# Stabilizer_Pounder.net
KiCad netlist of a schematic drawn in Altium Designer
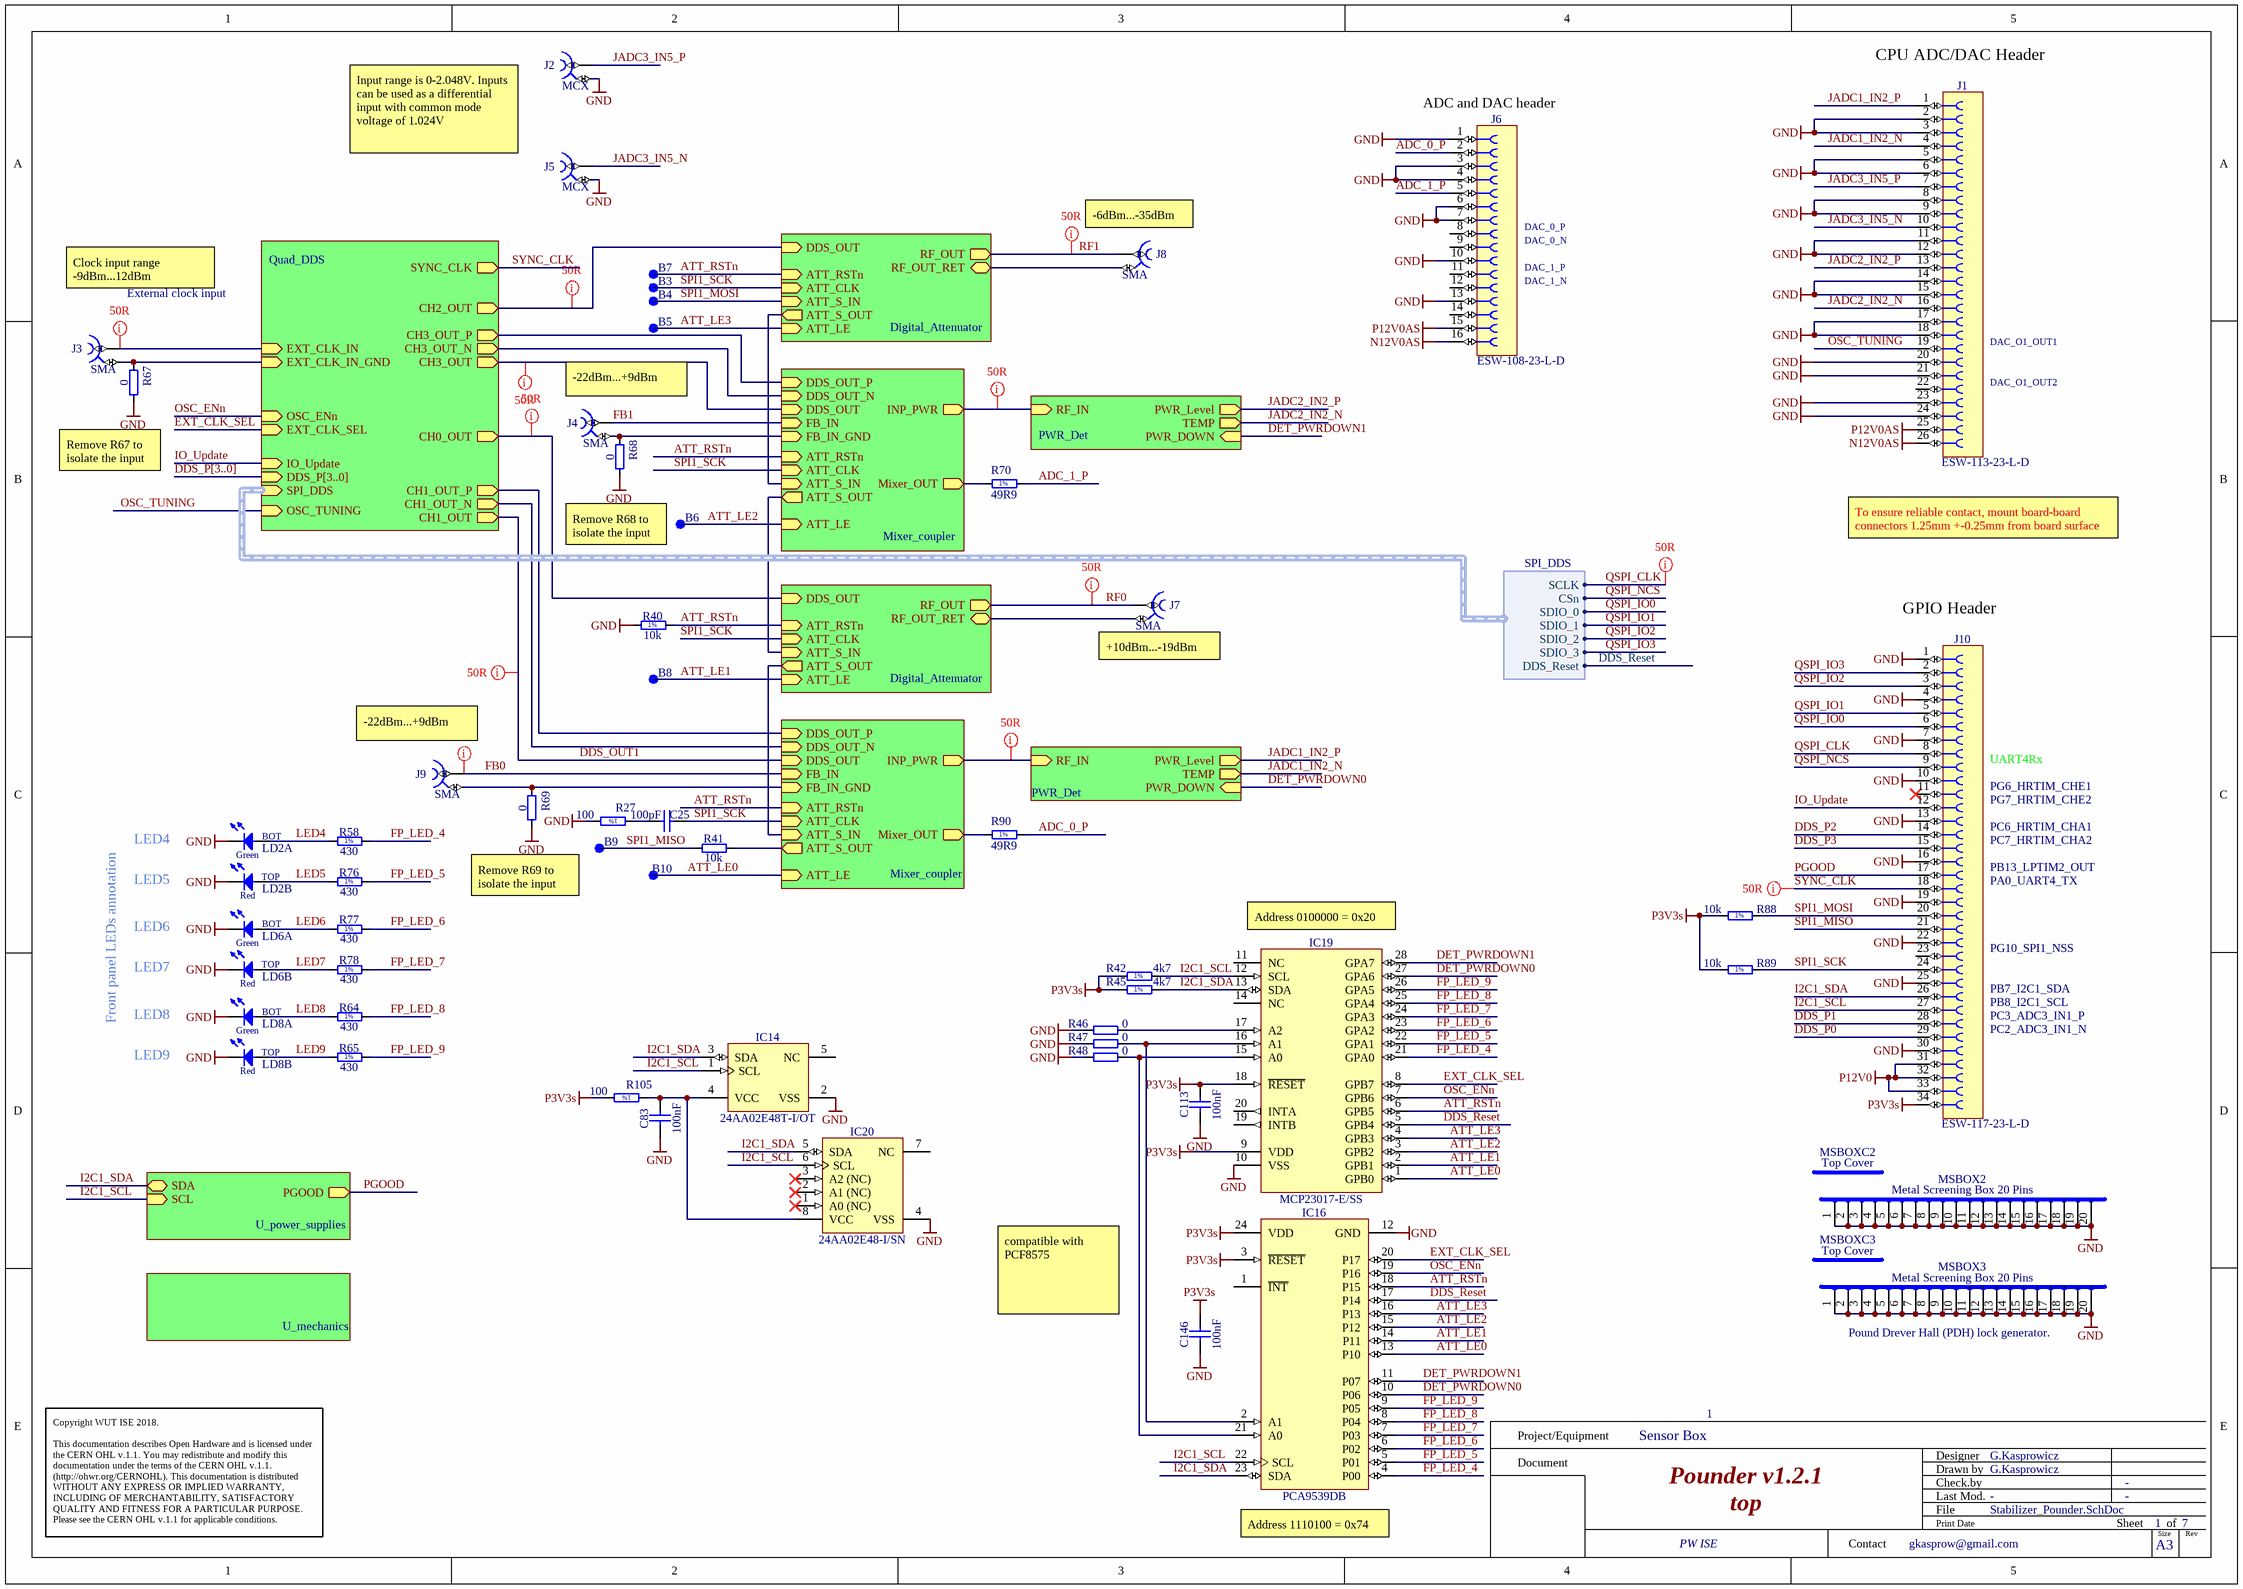
[diagram p0: Stabilizer_Pounder.SchDoc]

(export (version "E")
  (design (tool "Eeschema 10.0.6"))
  (components
    (comp (ref "B3")
      (value "SMD Pad")
      (footprint "C100")
      (description "Through Hole Pad")
      (fields (field (name "PART NUMBER") "SMD_PAD_D1MM") (field (name "AUTHOR") "CERN DEM JLC"))
      (libsource (lib "Eletro-mechanical") (part "Single SMD Pad (Round)"))
    )
    (comp (ref "B4")
      (value "SMD Pad")
      (footprint "C100")
      (description "Through Hole Pad")
      (fields (field (name "PART NUMBER") "SMD_PAD_D1MM") (field (name "AUTHOR") "CERN DEM JLC"))
      (libsource (lib "Eletro-mechanical") (part "Single SMD Pad (Round)"))
    )
    (comp (ref "B5")
      (value "SMD Pad")
      (footprint "C100")
      (description "Through Hole Pad")
      (fields (field (name "PART NUMBER") "SMD_PAD_D1MM") (field (name "AUTHOR") "CERN DEM JLC"))
      (libsource (lib "Eletro-mechanical") (part "Single SMD Pad (Round)"))
    )
    (comp (ref "B6")
      (value "SMD Pad")
      (footprint "C100")
      (description "Through Hole Pad")
      (fields (field (name "PART NUMBER") "SMD_PAD_D1MM") (field (name "AUTHOR") "CERN DEM JLC"))
      (libsource (lib "Eletro-mechanical") (part "Single SMD Pad (Round)"))
    )
    (comp (ref "B7")
      (value "SMD Pad")
      (footprint "C100")
      (description "Through Hole Pad")
      (fields (field (name "PART NUMBER") "SMD_PAD_D1MM") (field (name "AUTHOR") "CERN DEM JLC"))
      (libsource (lib "Eletro-mechanical") (part "Single SMD Pad (Round)"))
    )
    (comp (ref "B8")
      (value "SMD Pad")
      (footprint "C100")
      (description "Through Hole Pad")
      (fields (field (name "PART NUMBER") "SMD_PAD_D1MM") (field (name "AUTHOR") "CERN DEM JLC"))
      (libsource (lib "Eletro-mechanical") (part "Single SMD Pad (Round)"))
    )
    (comp (ref "B9")
      (value "SMD Pad")
      (footprint "C100")
      (description "Through Hole Pad")
      (fields (field (name "PART NUMBER") "SMD_PAD_D1MM") (field (name "AUTHOR") "CERN DEM JLC"))
      (libsource (lib "Eletro-mechanical") (part "Single SMD Pad (Round)"))
    )
    (comp (ref "B10")
      (value "SMD Pad")
      (footprint "C100")
      (description "Through Hole Pad")
      (fields (field (name "PART NUMBER") "SMD_PAD_D1MM") (field (name "AUTHOR") "CERN DEM JLC"))
      (libsource (lib "Eletro-mechanical") (part "Single SMD Pad (Round)"))
    )
    (comp (ref "C25")
      (value "100pF")
      (footprint "CAPC1005X55N")
      (description "Non-polarised capacitor")
      (fields
        (field (name "PART NUMBER") "CC0402_100PF_50V_5%_C0G")
        (field (name "VOLTAGE") "50V")
        (field (name "AUTHOR") "CERN DEM JLC")
      )
      (libsource (lib "Capacitors") (part "Capacitor - non polarized"))
    )
    (comp (ref "C83")
      (value "100nF")
      (footprint "CAPC1005X55N")
      (description "Non-polarised capacitor")
      (fields
        (field (name "PART NUMBER") "CC0402_100NF_16V_10%_X5R")
        (field (name "VOLTAGE") "16V")
        (field (name "AUTHOR") "CERN DEM JLC")
      )
      (libsource (lib "Capacitors") (part "Capacitor - non polarized"))
    )
    (comp (ref "C113")
      (value "100nF")
      (footprint "CAPC1005X55N")
      (description "Non-polarised capacitor")
      (fields
        (field (name "PART NUMBER") "CC0402_100NF_16V_10%_X5R")
        (field (name "VOLTAGE") "16V")
        (field (name "AUTHOR") "CERN DEM JLC")
      )
      (libsource (lib "Capacitors") (part "Capacitor - non polarized"))
    )
    (comp (ref "C146")
      (value "100nF")
      (footprint "CAPC1005X55N")
      (description "Non-polarised capacitor")
      (fields
        (field (name "PART NUMBER") "CC0402_100NF_16V_10%_X5R")
        (field (name "VOLTAGE") "16V")
        (field (name "AUTHOR") "CERN DEM JLC")
      )
      (libsource (lib "Capacitors") (part "Capacitor - non polarized"))
    )
    (comp (ref "IC14")
      (value "24AA02E48T-I/OT")
      (footprint "SOT95P280X145-5N")
      (description "1.7V-5.5V, 2K I2C Serial EEPROM With EUI-48 Node Identity")
      (fields (field (name "MANUFACTURER") "MICROCHIP TECHNOLOGY") (field (name "AUTHOR") "CERN DEM MR"))
      (libsource (lib "ICs And Semiconductors") (part "24AA02E48T-I/OT"))
    )
    (comp (ref "IC16")
      (value "PCA9539DB")
      (footprint "SOP65P780X200-24N")
      (fields (field (name "MANUFACTURER") "TEXAS INSTRUMENTS") (field (name "AUTHOR") "CERN DEM HF"))
      (libsource (lib "ICs And Semiconductors") (part "PCA9539DB"))
    )
    (comp (ref "IC19")
      (value "MCP23017-E/SS")
      (footprint "SOP65P780X200-28N")
      (description "16-bit I/O Port Expander With Serial Interface")
      (fields (field (name "MANUFACTURER") "MICROCHIP TECHNOLOGY") (field (name "AUTHOR") "CERN DEM JLC"))
      (libsource (lib "ICs And Semiconductors") (part "MCP23017-E/SS"))
    )
    (comp (ref "IC20")
      (value "24AA02E48-I/SN")
      (footprint "SOIC127P600X175-8N")
      (description "1.7V-5.5V, 2K I2C™ Serial EEPROMs with EUI-48™ Node Identity")
      (fields (field (name "MANUFACTURER") "MICROCHIP TECHNOLOGY") (field (name "AUTHOR") "CERN DEM MR"))
      (libsource (lib "ICS-logic") (part "MEM_24AA02E48-I/SN"))
    )
    (comp (ref "J1")
      (value "ESW-113-23-L-D")
      (footprint "connectors:ESW-113-23-L-D")
      (description "Connector Elevated Socket 26 POS 2.54mm, 13.59mm height")
      (fields
        (field (name "MANUFACTURER") "Samtec")
        (field (name "MANUFACTURER PART NUMBER") "ESW-113-23-L-D")
      )
      (libsource (lib "connectors") (part "ESW-113-23-L-D"))
    )
    (comp (ref "J2")
      (value "MCX")
      (footprint "AMPHENOL_919-383J-51A")
      (fields
        (field (name "PART NUMBER") "AMPHENOL_919-383J-51A")
        (field (name "MANUFACTURER") "AMPHENOL")
        (field (name "MANUFACTURER PART NUMBER") "919-383J-51A")
        (field (name "AUTHOR") "CERN DEM BC")
      )
      (libsource (lib "Connectors") (part "Coax_1Female_1Shield"))
    )
    (comp (ref "J3")
      (value "SMA")
      (footprint "DELOCK_65848")
      (description "50 Ohm Through Hole SMA Right Angle PCB Jack")
      (fields
        (field (name "PART NUMBER") "DELOCK_65848")
        (field (name "MANUFACTURER") "DELOCK")
        (field (name "AUTHOR") "GK")
      )
      (libsource (lib "Connectors") (part "CON_SMA_DELOCK_65848"))
    )
    (comp (ref "J4")
      (value "SMA")
      (footprint "DELOCK_65848")
      (description "50 Ohm Through Hole SMA Right Angle PCB Jack")
      (fields
        (field (name "PART NUMBER") "DELOCK_65848")
        (field (name "MANUFACTURER") "DELOCK")
        (field (name "AUTHOR") "GK")
      )
      (libsource (lib "Connectors") (part "CON_SMA_DELOCK_65848"))
    )
    (comp (ref "J5")
      (value "MCX")
      (footprint "AMPHENOL_919-383J-51A")
      (fields
        (field (name "PART NUMBER") "AMPHENOL_919-383J-51A")
        (field (name "MANUFACTURER") "AMPHENOL")
        (field (name "MANUFACTURER PART NUMBER") "919-383J-51A")
        (field (name "AUTHOR") "CERN DEM BC")
      )
      (libsource (lib "Connectors") (part "Coax_1Female_1Shield"))
    )
    (comp (ref "J6")
      (value "ESW-108-23-L-D")
      (footprint "connectors:ESW-108-23-L-D")
      (description "Connector Elevated Socket 16 POS 2.54mm, 13.59mm height")
      (fields
        (field (name "MANUFACTURER") "Samtec")
        (field (name "MANUFACTURER PART NUMBER") "ESW-108-23-L-D")
      )
      (libsource (lib "connectors") (part "ESW-108-23-L-D"))
    )
    (comp (ref "J7")
      (value "SMA")
      (footprint "DELOCK_65848")
      (description "50 Ohm Through Hole SMA Right Angle PCB Jack")
      (fields
        (field (name "PART NUMBER") "DELOCK_65848")
        (field (name "MANUFACTURER") "DELOCK")
        (field (name "AUTHOR") "GK")
      )
      (libsource (lib "") (part "CON_SMA_DELOCK_65848_1"))
    )
    (comp (ref "J8")
      (value "SMA")
      (footprint "DELOCK_65848")
      (description "50 Ohm Through Hole SMA Right Angle PCB Jack")
      (fields
        (field (name "PART NUMBER") "DELOCK_65848")
        (field (name "MANUFACTURER") "DELOCK")
        (field (name "AUTHOR") "GK")
      )
      (libsource (lib "") (part "CON_SMA_DELOCK_65848_1"))
    )
    (comp (ref "J9")
      (value "SMA")
      (footprint "DELOCK_65848")
      (description "50 Ohm Through Hole SMA Right Angle PCB Jack")
      (fields
        (field (name "PART NUMBER") "DELOCK_65848")
        (field (name "MANUFACTURER") "DELOCK")
        (field (name "AUTHOR") "GK")
      )
      (libsource (lib "Connectors") (part "CON_SMA_DELOCK_65848"))
    )
    (comp (ref "J10")
      (value "ESW-117-23-L-D")
      (footprint "connectors:ESW-117-23-L-D")
      (description "Connector Elevated Socket 34 POS 2.54mm, 13.59mm height")
      (fields
        (field (name "MANUFACTURER") "Samtec")
        (field (name "MANUFACTURER PART NUMBER") "ESW-117-23-L-D")
      )
      (libsource (lib "connectors") (part "ESW-117-23-L-D"))
    )
    (comp (ref "LD2")
      (value "Red/Green")
      (footprint "LED_DIALIGHT_571-0112F")
      (description "2x LED  Botom Green, Top Red")
      (fields
        (field (name "PART NUMBER") "LED_DIALIGHT_571-0112F")
        (field (name "MANUFACTURER") "DIALIGHT")
        (field (name "AUTHOR") "CERN DEM JLC")
      )
      (libsource (lib "ICs And Semiconductors") (part "LED x2 G-1C2A-BOT_R-3C4A-TOP"))
    )
    (comp (ref "LD6")
      (value "Red/Green")
      (footprint "LED_DIALIGHT_571-0112F")
      (description "2x LED  Botom Green, Top Red")
      (fields
        (field (name "PART NUMBER") "LED_DIALIGHT_571-0112F")
        (field (name "MANUFACTURER") "DIALIGHT")
        (field (name "AUTHOR") "CERN DEM JLC")
      )
      (libsource (lib "ICs And Semiconductors") (part "LED x2 G-1C2A-BOT_R-3C4A-TOP"))
    )
    (comp (ref "LD8")
      (value "Red/Green")
      (footprint "LED_DIALIGHT_571-0112F")
      (description "2x LED  Botom Green, Top Red")
      (fields
        (field (name "PART NUMBER") "LED_DIALIGHT_571-0112F")
        (field (name "MANUFACTURER") "DIALIGHT")
        (field (name "AUTHOR") "CERN DEM JLC")
      )
      (libsource (lib "ICs And Semiconductors") (part "LED x2 G-1C2A-BOT_R-3C4A-TOP"))
    )
    (comp (ref "MSBOX2")
      (value "Metal Screening Box 20 Pins")
      (footprint "MSBOX_LAIRD_BMI-S-205-F")
      (fields
        (field (name "PART NUMBER") "MSBOX_LAIRD_BMI-S-205-F")
        (field (name "MANUFACTURER") "LAIRD")
        (field (name "MANUFACTURER PART NUMBER") "BMI-S-205-F")
        (field (name "AUTHOR") "CERN DEM JLC")
      )
      (libsource (lib "Eletro-mechanical") (part "Metal Screening Box - 20 pins"))
    )
    (comp (ref "MSBOX3")
      (value "Metal Screening Box 20 Pins")
      (footprint "MSBOX_LAIRD_BMI-S-205-F")
      (fields
        (field (name "PART NUMBER") "MSBOX_LAIRD_BMI-S-205-F")
        (field (name "MANUFACTURER") "LAIRD")
        (field (name "MANUFACTURER PART NUMBER") "BMI-S-205-F")
        (field (name "AUTHOR") "CERN DEM JLC")
      )
      (libsource (lib "Eletro-mechanical") (part "Metal Screening Box - 20 pins"))
    )
    (comp (ref "MSBOXC2")
      (value "Top Cover")
      (footprint "MSBOX_LAIRD_BMI-S-205-C")
      (description "Metal Screening Box - Top Cover 0 Pin")
      (fields
        (field (name "PART NUMBER") "MSBOX_LAIRD_BMI-S-205-C")
        (field (name "MANUFACTURER") "LAIRD")
        (field (name "AUTHOR") "CERN DEM JLC")
      )
      (libsource (lib "Eletro-mechanical") (part "Metal Screening Box - Top Cover"))
    )
    (comp (ref "MSBOXC3")
      (value "Top Cover")
      (footprint "MSBOX_LAIRD_BMI-S-205-C")
      (description "Metal Screening Box - Top Cover 0 Pin")
      (fields
        (field (name "PART NUMBER") "MSBOX_LAIRD_BMI-S-205-C")
        (field (name "MANUFACTURER") "LAIRD")
        (field (name "AUTHOR") "CERN DEM JLC")
      )
      (libsource (lib "Eletro-mechanical") (part "Metal Screening Box - Top Cover"))
    )
    (comp (ref "R27")
      (value "100")
      (footprint "RESC1005X40N")
      (description "Resistor - 1%")
      (fields
        (field (name "PART NUMBER") "R0402_100R_1%_0.0625W_100PPM")
        (field (name "POWER") "0.0625W")
        (field (name "AUTHOR") "CERN DEM JLC")
      )
      (libsource (lib "Resistors") (part "Resistor - 1%"))
    )
    (comp (ref "R40")
      (value "10k")
      (footprint "RESC1005X40N")
      (description "Resistor - 1%")
      (fields
        (field (name "PART NUMBER") "R0402_10K_1%_0.0625W_100PPM")
        (field (name "POWER") "0.0625W")
        (field (name "AUTHOR") "CERN DEM JLC")
      )
      (libsource (lib "Resistors") (part "Resistor - 1%"))
    )
    (comp (ref "R41")
      (value "10k")
      (footprint "RESC1005X40N")
      (description "Resistor - 1%")
      (fields
        (field (name "PART NUMBER") "R0402_10K_1%_0.0625W_100PPM")
        (field (name "POWER") "0.0625W")
        (field (name "AUTHOR") "CERN DEM JLC")
      )
      (libsource (lib "") (part "Resistor - 1%_1"))
    )
    (comp (ref "R42")
      (value "4k7")
      (footprint "RESC1005X40N")
      (description "Resistor - 1%")
      (fields
        (field (name "PART NUMBER") "R0402_4K7_1%_0.0625W_100PPM")
        (field (name "POWER") "0.0625W")
        (field (name "AUTHOR") "CERN DEM JLC")
      )
      (libsource (lib "Resistors") (part "Resistor - 1%"))
    )
    (comp (ref "R45")
      (value "4k7")
      (footprint "RESC1005X40N")
      (description "Resistor - 1%")
      (fields
        (field (name "PART NUMBER") "R0402_4K7_1%_0.0625W_100PPM")
        (field (name "POWER") "0.0625W")
        (field (name "AUTHOR") "CERN DEM JLC")
      )
      (libsource (lib "Resistors") (part "Resistor - 1%"))
    )
    (comp (ref "R46")
      (value "0")
      (footprint "RESC1005X40N")
      (description "Resistor")
      (fields
        (field (name "PART NUMBER") "R0402_0R_JUMPER")
        (field (name "MANUFACTURER") "GENERIC")
        (field (name "AUTHOR") "CERN DEM JLC")
      )
      (libsource (lib "Resistors") (part "Resistor"))
    )
    (comp (ref "R47")
      (value "0")
      (footprint "RESC1005X40N")
      (description "Resistor")
      (fields
        (field (name "PART NUMBER") "R0402_0R_JUMPER")
        (field (name "MANUFACTURER") "GENERIC")
        (field (name "AUTHOR") "CERN DEM JLC")
      )
      (libsource (lib "Resistors") (part "Resistor"))
    )
    (comp (ref "R48")
      (value "0")
      (footprint "RESC1005X40N")
      (description "Resistor")
      (fields
        (field (name "PART NUMBER") "R0402_0R_JUMPER")
        (field (name "MANUFACTURER") "GENERIC")
        (field (name "AUTHOR") "CERN DEM JLC")
      )
      (libsource (lib "Resistors") (part "Resistor"))
    )
    (comp (ref "R58")
      (value "430")
      (footprint "RESC1608X55N")
      (description "Resistor - 1%")
      (fields
        (field (name "PART NUMBER") "R0603_430R_1%_0.1W_100PPM")
        (field (name "POWER") "0.1W")
        (field (name "AUTHOR") "CERN DEM JLC")
      )
      (libsource (lib "Resistors") (part "Resistor - 1%"))
    )
    (comp (ref "R64")
      (value "430")
      (footprint "RESC1608X55N")
      (description "Resistor - 1%")
      (fields
        (field (name "PART NUMBER") "R0603_430R_1%_0.1W_100PPM")
        (field (name "POWER") "0.1W")
        (field (name "AUTHOR") "CERN DEM JLC")
      )
      (libsource (lib "Resistors") (part "Resistor - 1%"))
    )
    (comp (ref "R65")
      (value "430")
      (footprint "RESC1608X55N")
      (description "Resistor - 1%")
      (fields
        (field (name "PART NUMBER") "R0603_430R_1%_0.1W_100PPM")
        (field (name "POWER") "0.1W")
        (field (name "AUTHOR") "CERN DEM JLC")
      )
      (libsource (lib "Resistors") (part "Resistor - 1%"))
    )
    (comp (ref "R67")
      (value "0")
      (footprint "RESC1608X55N")
      (description "Resistor")
      (fields
        (field (name "PART NUMBER") "R0603_0R_JUMPER")
        (field (name "MANUFACTURER") "GENERIC")
        (field (name "AUTHOR") "CERN DEM JLC")
      )
      (libsource (lib "Resistors") (part "Resistor"))
    )
    (comp (ref "R68")
      (value "0")
      (footprint "RESC1608X55N")
      (description "Resistor")
      (fields
        (field (name "PART NUMBER") "R0603_0R_JUMPER")
        (field (name "MANUFACTURER") "GENERIC")
        (field (name "AUTHOR") "CERN DEM JLC")
      )
      (libsource (lib "Resistors") (part "Resistor"))
    )
    (comp (ref "R69")
      (value "0")
      (footprint "RESC1608X55N")
      (description "Resistor")
      (fields
        (field (name "PART NUMBER") "R0603_0R_JUMPER")
        (field (name "MANUFACTURER") "GENERIC")
        (field (name "AUTHOR") "CERN DEM JLC")
      )
      (libsource (lib "Resistors") (part "Resistor"))
    )
    (comp (ref "R70")
      (value "49R9")
      (footprint "RESC1608X55N")
      (description "Resistor - 1%")
      (fields
        (field (name "PART NUMBER") "R0603_49R9_1%_0.1W_100PPM")
        (field (name "POWER") "0.1W")
        (field (name "AUTHOR") "CERN DEM JLC")
      )
      (libsource (lib "Resistors") (part "Resistor - 1%"))
    )
    (comp (ref "R76")
      (value "430")
      (footprint "RESC1608X55N")
      (description "Resistor - 1%")
      (fields
        (field (name "PART NUMBER") "R0603_430R_1%_0.1W_100PPM")
        (field (name "POWER") "0.1W")
        (field (name "AUTHOR") "CERN DEM JLC")
      )
      (libsource (lib "Resistors") (part "Resistor - 1%"))
    )
    (comp (ref "R77")
      (value "430")
      (footprint "RESC1608X55N")
      (description "Resistor - 1%")
      (fields
        (field (name "PART NUMBER") "R0603_430R_1%_0.1W_100PPM")
        (field (name "POWER") "0.1W")
        (field (name "AUTHOR") "CERN DEM JLC")
      )
      (libsource (lib "Resistors") (part "Resistor - 1%"))
    )
    (comp (ref "R78")
      (value "430")
      (footprint "RESC1608X55N")
      (description "Resistor - 1%")
      (fields
        (field (name "PART NUMBER") "R0603_430R_1%_0.1W_100PPM")
        (field (name "POWER") "0.1W")
        (field (name "AUTHOR") "CERN DEM JLC")
      )
      (libsource (lib "Resistors") (part "Resistor - 1%"))
    )
    (comp (ref "R88")
      (value "10k")
      (footprint "RESC1005X40N")
      (description "Resistor - 1%")
      (fields
        (field (name "PART NUMBER") "R0402_10K_1%_0.0625W_100PPM")
        (field (name "POWER") "0.0625W")
        (field (name "AUTHOR") "CERN DEM JLC")
      )
      (libsource (lib "Resistors") (part "Resistor - 1%"))
    )
    (comp (ref "R89")
      (value "10k")
      (footprint "RESC1005X40N")
      (description "Resistor - 1%")
      (fields
        (field (name "PART NUMBER") "R0402_10K_1%_0.0625W_100PPM")
        (field (name "POWER") "0.0625W")
        (field (name "AUTHOR") "CERN DEM JLC")
      )
      (libsource (lib "Resistors") (part "Resistor - 1%"))
    )
    (comp (ref "R90")
      (value "49R9")
      (footprint "RESC1608X55N")
      (description "Resistor - 1%")
      (fields
        (field (name "PART NUMBER") "R0603_49R9_1%_0.1W_100PPM")
        (field (name "POWER") "0.1W")
        (field (name "AUTHOR") "CERN DEM JLC")
      )
      (libsource (lib "Resistors") (part "Resistor - 1%"))
    )
    (comp (ref "R105")
      (value "100")
      (footprint "RESC1005X40N")
      (description "Resistor - 1%")
      (fields
        (field (name "PART NUMBER") "R0402_100R_1%_0.0625W_100PPM")
        (field (name "POWER") "0.0625W")
        (field (name "AUTHOR") "CERN DEM JLC")
      )
      (libsource (lib "Resistors") (part "Resistor - 1%"))
    )
  )
  (nets
    (net (code "2") (name "/ADC_0_P") (class "Default")
      (node (ref "J6") (pin "2") (pinfunction "2_2") (pintype "bidirectional"))
      (node (ref "R90") (pin "2") (pinfunction "2_2") (pintype "passive"))
    )
    (net (code "3") (name "/ADC_1_P") (class "Default")
      (node (ref "J6") (pin "5") (pinfunction "5_5") (pintype "bidirectional"))
      (node (ref "R70") (pin "2") (pinfunction "2_2") (pintype "passive"))
    )
    (net (code "4") (name "/ATT_LE0") (class "Default")
      (node (ref "B10") (pin "1") (pinfunction "1_1") (pintype "bidirectional"))
      (node (ref "IC16") (pin "13") (pinfunction "P10_13") (pintype "bidirectional"))
      (node (ref "IC19") (pin "1") (pinfunction "GPB0_1") (pintype "bidirectional"))
    )
    (net (code "5") (name "/ATT_LE1") (class "Default")
      (node (ref "B8") (pin "1") (pinfunction "1_1") (pintype "bidirectional"))
      (node (ref "IC16") (pin "14") (pinfunction "P11_14") (pintype "bidirectional"))
      (node (ref "IC19") (pin "2") (pinfunction "GPB1_2") (pintype "bidirectional"))
    )
    (net (code "6") (name "/ATT_LE2") (class "Default")
      (node (ref "B6") (pin "1") (pinfunction "1_1") (pintype "bidirectional"))
      (node (ref "IC16") (pin "15") (pinfunction "P12_15") (pintype "bidirectional"))
      (node (ref "IC19") (pin "3") (pinfunction "GPB2_3") (pintype "bidirectional"))
    )
    (net (code "7") (name "/ATT_LE3") (class "Default")
      (node (ref "B5") (pin "1") (pinfunction "1_1") (pintype "bidirectional"))
      (node (ref "IC16") (pin "16") (pinfunction "P13_16") (pintype "bidirectional"))
      (node (ref "IC19") (pin "4") (pinfunction "GPB3_4") (pintype "bidirectional"))
    )
    (net (code "8") (name "/ATT_RSTn") (class "Default")
      (node (ref "B7") (pin "1") (pinfunction "1_1") (pintype "bidirectional"))
      (node (ref "IC16") (pin "18") (pinfunction "P15_18") (pintype "bidirectional"))
      (node (ref "IC19") (pin "6") (pinfunction "GPB5_6") (pintype "bidirectional"))
      (node (ref "R40") (pin "2") (pinfunction "2_2") (pintype "passive"))
    )
    (net (code "9") (name "/ATT_S_OUT") (class "Default")
      (node (ref "R41") (pin "2") (pinfunction "2_2") (pintype "passive"))
    )
    (net (code "21") (name "/DDS_P0") (class "Default")
      (node (ref "J10") (pin "29") (pinfunction "29_29") (pintype "bidirectional"))
    )
    (net (code "22") (name "/DDS_P1") (class "Default")
      (node (ref "J10") (pin "28") (pinfunction "28_28") (pintype "bidirectional"))
    )
    (net (code "23") (name "/DDS_P2") (class "Default")
      (node (ref "J10") (pin "14") (pinfunction "14_14") (pintype "bidirectional"))
    )
    (net (code "24") (name "/DDS_P3") (class "Default")
      (node (ref "J10") (pin "15") (pinfunction "15_15") (pintype "bidirectional"))
    )
    (net (code "26") (name "/DDS_Reset") (class "Default")
      (node (ref "IC16") (pin "17") (pinfunction "P14_17") (pintype "bidirectional"))
      (node (ref "IC19") (pin "5") (pinfunction "GPB4_5") (pintype "bidirectional"))
    )
    (net (code "27") (name "/DET_PWRDOWN0") (class "Default")
      (node (ref "IC16") (pin "10") (pinfunction "P06_10") (pintype "bidirectional"))
      (node (ref "IC19") (pin "27") (pinfunction "GPA6_27") (pintype "bidirectional"))
    )
    (net (code "28") (name "/DET_PWRDOWN1") (class "Default")
      (node (ref "IC16") (pin "11") (pinfunction "P07_11") (pintype "bidirectional"))
      (node (ref "IC19") (pin "28") (pinfunction "GPA7_28") (pintype "bidirectional"))
    )
    (net (code "29") (name "/EXT_CLK_IN") (class "Default")
      (node (ref "J3") (pin "1") (pinfunction "1_1") (pintype "bidirectional"))
    )
    (net (code "30") (name "/EXT_CLK_IN_GND") (class "Default")
      (node (ref "J3") (pin "2") (pinfunction "2_2") (pintype "bidirectional"))
      (node (ref "R67") (pin "1") (pinfunction "1_1") (pintype "passive"))
    )
    (net (code "31") (name "/EXT_CLK_SEL") (class "Default")
      (node (ref "IC16") (pin "20") (pinfunction "P17_20") (pintype "bidirectional"))
      (node (ref "IC19") (pin "8") (pinfunction "GPB7_8") (pintype "bidirectional"))
    )
    (net (code "32") (name "/FB0") (class "Default")
      (node (ref "J9") (pin "1") (pinfunction "1_1") (pintype "bidirectional"))
    )
    (net (code "33") (name "/FB1") (class "Default")
      (node (ref "J4") (pin "1") (pinfunction "1_1") (pintype "bidirectional"))
    )
    (net (code "34") (name "/FB_IN_GND") (class "Default")
      (node (ref "J9") (pin "2") (pinfunction "2_2") (pintype "bidirectional"))
      (node (ref "R69") (pin "1") (pinfunction "1_1") (pintype "passive"))
    )
    (net (code "35") (name "/FB_IN_GND_1") (class "Default")
      (node (ref "J4") (pin "2") (pinfunction "2_2") (pintype "bidirectional"))
      (node (ref "R68") (pin "1") (pinfunction "1_1") (pintype "passive"))
    )
    (net (code "36") (name "/FP_LED_4") (class "Default")
      (node (ref "IC16") (pin "4") (pinfunction "P00_4") (pintype "bidirectional"))
      (node (ref "IC19") (pin "21") (pinfunction "GPA0_21") (pintype "bidirectional"))
      (node (ref "R58") (pin "2") (pinfunction "2_2") (pintype "passive"))
    )
    (net (code "37") (name "/FP_LED_5") (class "Default")
      (node (ref "IC16") (pin "5") (pinfunction "P01_5") (pintype "bidirectional"))
      (node (ref "IC19") (pin "22") (pinfunction "GPA1_22") (pintype "bidirectional"))
      (node (ref "R76") (pin "2") (pinfunction "2_2") (pintype "passive"))
    )
    (net (code "38") (name "/FP_LED_6") (class "Default")
      (node (ref "IC16") (pin "6") (pinfunction "P02_6") (pintype "bidirectional"))
      (node (ref "IC19") (pin "23") (pinfunction "GPA2_23") (pintype "bidirectional"))
      (node (ref "R77") (pin "2") (pinfunction "2_2") (pintype "passive"))
    )
    (net (code "39") (name "/FP_LED_7") (class "Default")
      (node (ref "IC16") (pin "7") (pinfunction "P03_7") (pintype "bidirectional"))
      (node (ref "IC19") (pin "24") (pinfunction "GPA3_24") (pintype "bidirectional"))
      (node (ref "R78") (pin "2") (pinfunction "2_2") (pintype "passive"))
    )
    (net (code "40") (name "/FP_LED_8") (class "Default")
      (node (ref "IC16") (pin "8") (pinfunction "P04_8") (pintype "bidirectional"))
      (node (ref "IC19") (pin "25") (pinfunction "GPA4_25") (pintype "bidirectional"))
      (node (ref "R64") (pin "2") (pinfunction "2_2") (pintype "passive"))
    )
    (net (code "41") (name "/FP_LED_9") (class "Default")
      (node (ref "IC16") (pin "9") (pinfunction "P05_9") (pintype "bidirectional"))
      (node (ref "IC19") (pin "26") (pinfunction "GPA5_26") (pintype "bidirectional"))
      (node (ref "R65") (pin "2") (pinfunction "2_2") (pintype "passive"))
    )
    (net (code "42") (name "/I2C1_SCL") (class "Default")
      (node (ref "IC14") (pin "1") (pinfunction "SCL_1") (pintype "input"))
      (node (ref "IC16") (pin "22") (pinfunction "SCL_22") (pintype "input"))
      (node (ref "IC19") (pin "12") (pinfunction "SCL_12") (pintype "input"))
      (node (ref "IC20") (pin "6") (pinfunction "SCL_6") (pintype "input"))
      (node (ref "J10") (pin "27") (pinfunction "27_27") (pintype "bidirectional"))
      (node (ref "R42") (pin "2") (pinfunction "2_2") (pintype "passive"))
    )
    (net (code "43") (name "/I2C1_SDA") (class "Default")
      (node (ref "IC14") (pin "3") (pinfunction "SDA_3") (pintype "bidirectional"))
      (node (ref "IC16") (pin "23") (pinfunction "SDA_23") (pintype "bidirectional"))
      (node (ref "IC19") (pin "13") (pinfunction "SDA_13") (pintype "bidirectional"))
      (node (ref "IC20") (pin "5") (pinfunction "SDA_5") (pintype "bidirectional"))
      (node (ref "J10") (pin "26") (pinfunction "26_26") (pintype "bidirectional"))
      (node (ref "R45") (pin "2") (pinfunction "2_2") (pintype "passive"))
    )
    (net (code "46") (name "/IO_Update") (class "Default")
      (node (ref "J10") (pin "12") (pinfunction "12_12") (pintype "bidirectional"))
    )
    (net (code "47") (name "/JADC1_IN2_N") (class "Default")
      (node (ref "J1") (pin "4") (pinfunction "4_4") (pintype "bidirectional"))
    )
    (net (code "48") (name "/JADC1_IN2_P") (class "Default")
      (node (ref "J1") (pin "1") (pinfunction "1_1") (pintype "bidirectional"))
    )
    (net (code "49") (name "/JADC2_IN2_N") (class "Default")
      (node (ref "J1") (pin "16") (pinfunction "16_16") (pintype "bidirectional"))
    )
    (net (code "50") (name "/JADC2_IN2_P") (class "Default")
      (node (ref "J1") (pin "13") (pinfunction "13_13") (pintype "bidirectional"))
    )
    (net (code "51") (name "/JADC3_IN5_N") (class "Default")
      (node (ref "J1") (pin "10") (pinfunction "10_10") (pintype "bidirectional"))
      (node (ref "J5") (pin "1") (pinfunction "1_1") (pintype "bidirectional"))
    )
    (net (code "52") (name "/JADC3_IN5_P") (class "Default")
      (node (ref "J1") (pin "7") (pinfunction "7_7") (pintype "bidirectional"))
      (node (ref "J2") (pin "1") (pinfunction "1_1") (pintype "bidirectional"))
    )
    (net (code "53") (name "/LED4") (class "Default")
      (node (ref "LD2") (pin "2") (pinfunction "A_2") (pintype "passive"))
      (node (ref "R58") (pin "1") (pinfunction "1_1") (pintype "passive"))
    )
    (net (code "54") (name "/LED5") (class "Default")
      (node (ref "LD2") (pin "4") (pinfunction "A_4") (pintype "passive"))
      (node (ref "R76") (pin "1") (pinfunction "1_1") (pintype "passive"))
    )
    (net (code "55") (name "/LED6") (class "Default")
      (node (ref "LD6") (pin "2") (pinfunction "A_2") (pintype "passive"))
      (node (ref "R77") (pin "1") (pinfunction "1_1") (pintype "passive"))
    )
    (net (code "56") (name "/LED7") (class "Default")
      (node (ref "LD6") (pin "4") (pinfunction "A_4") (pintype "passive"))
      (node (ref "R78") (pin "1") (pinfunction "1_1") (pintype "passive"))
    )
    (net (code "57") (name "/LED8") (class "Default")
      (node (ref "LD8") (pin "2") (pinfunction "A_2") (pintype "passive"))
      (node (ref "R64") (pin "1") (pinfunction "1_1") (pintype "passive"))
    )
    (net (code "58") (name "/LED9") (class "Default")
      (node (ref "LD8") (pin "4") (pinfunction "A_4") (pintype "passive"))
      (node (ref "R65") (pin "1") (pinfunction "1_1") (pintype "passive"))
    )
    (net (code "59") (name "/Mixer_OUT") (class "Default")
      (node (ref "R90") (pin "1") (pinfunction "1_1") (pintype "passive"))
    )
    (net (code "60") (name "/Mixer_OUT_1") (class "Default")
      (node (ref "R70") (pin "1") (pinfunction "1_1") (pintype "passive"))
    )
    (net (code "61") (name "/OSC_ENn") (class "Default")
      (node (ref "IC16") (pin "19") (pinfunction "P16_19") (pintype "bidirectional"))
      (node (ref "IC19") (pin "7") (pinfunction "GPB6_7") (pintype "bidirectional"))
    )
    (net (code "62") (name "/OSC_TUNING") (class "Default")
      (node (ref "J1") (pin "19") (pinfunction "19_19") (pintype "bidirectional"))
    )
    (net (code "63") (name "/PGOOD") (class "Default")
      (node (ref "J10") (pin "17") (pinfunction "17_17") (pintype "bidirectional"))
    )
    (net (code "64") (name "/QSPI_CLK") (class "Default")
      (node (ref "J10") (pin "8") (pinfunction "8_8") (pintype "bidirectional"))
    )
    (net (code "65") (name "/QSPI_IO0") (class "Default")
      (node (ref "J10") (pin "6") (pinfunction "6_6") (pintype "bidirectional"))
    )
    (net (code "66") (name "/QSPI_IO1") (class "Default")
      (node (ref "J10") (pin "5") (pinfunction "5_5") (pintype "bidirectional"))
    )
    (net (code "67") (name "/QSPI_IO2") (class "Default")
      (node (ref "J10") (pin "3") (pinfunction "3_3") (pintype "bidirectional"))
    )
    (net (code "68") (name "/QSPI_IO3") (class "Default")
      (node (ref "J10") (pin "2") (pinfunction "2_2") (pintype "bidirectional"))
    )
    (net (code "69") (name "/QSPI_NCS") (class "Default")
      (node (ref "J10") (pin "9") (pinfunction "9_9") (pintype "bidirectional"))
    )
    (net (code "70") (name "/RF0") (class "Default")
      (node (ref "J7") (pin "1") (pinfunction "1_1") (pintype "bidirectional"))
    )
    (net (code "71") (name "/RF1") (class "Default")
      (node (ref "J8") (pin "1") (pinfunction "1_1") (pintype "bidirectional"))
    )
    (net (code "72") (name "/RF_OUT_RET") (class "Default")
      (node (ref "J7") (pin "2") (pinfunction "2_2") (pintype "bidirectional"))
    )
    (net (code "73") (name "/RF_OUT_RET_1") (class "Default")
      (node (ref "J8") (pin "2") (pinfunction "2_2") (pintype "bidirectional"))
    )
    (net (code "74") (name "/SPI1_MISO") (class "Default")
      (node (ref "B9") (pin "1") (pinfunction "1_1") (pintype "bidirectional"))
      (node (ref "J10") (pin "21") (pinfunction "21_21") (pintype "bidirectional"))
      (node (ref "R41") (pin "1") (pinfunction "1_1") (pintype "passive"))
    )
    (net (code "75") (name "/SPI1_MOSI") (class "Default")
      (node (ref "B4") (pin "1") (pinfunction "1_1") (pintype "bidirectional"))
      (node (ref "J10") (pin "20") (pinfunction "20_20") (pintype "bidirectional"))
      (node (ref "R88") (pin "2") (pinfunction "2_2") (pintype "passive"))
    )
    (net (code "76") (name "/SPI1_SCK") (class "Default")
      (node (ref "B3") (pin "1") (pinfunction "1_1") (pintype "bidirectional"))
      (node (ref "C25") (pin "2") (pinfunction "2_2") (pintype "passive"))
      (node (ref "J10") (pin "24") (pinfunction "24_24") (pintype "bidirectional"))
      (node (ref "R89") (pin "2") (pinfunction "2_2") (pintype "passive"))
    )
    (net (code "77") (name "/SYNC_CLK") (class "Default")
      (node (ref "J10") (pin "18") (pinfunction "18_18") (pintype "bidirectional"))
    )
    (net (code "79") (name "GND") (class "Default")
      (node (ref "C113") (pin "1") (pinfunction "1_1") (pintype "passive"))
      (node (ref "C146") (pin "1") (pinfunction "1_1") (pintype "passive"))
      (node (ref "C83") (pin "1") (pinfunction "1_1") (pintype "passive"))
      (node (ref "IC14") (pin "2") (pinfunction "VSS_2") (pintype "power_in"))
      (node (ref "IC16") (pin "12") (pinfunction "GND_12") (pintype "power_in"))
      (node (ref "IC19") (pin "10") (pinfunction "VSS_10") (pintype "power_in"))
      (node (ref "IC20") (pin "4") (pinfunction "VSS_4") (pintype "power_in"))
      (node (ref "J1") (pin "11") (pinfunction "11_11") (pintype "bidirectional"))
      (node (ref "J1") (pin "12") (pinfunction "12_12") (pintype "bidirectional"))
      (node (ref "J1") (pin "14") (pinfunction "14_14") (pintype "bidirectional"))
      (node (ref "J1") (pin "15") (pinfunction "15_15") (pintype "bidirectional"))
      (node (ref "J1") (pin "17") (pinfunction "17_17") (pintype "bidirectional"))
      (node (ref "J1") (pin "18") (pinfunction "18_18") (pintype "bidirectional"))
      (node (ref "J1") (pin "2") (pinfunction "2_2") (pintype "bidirectional"))
      (node (ref "J1") (pin "20") (pinfunction "20_20") (pintype "bidirectional"))
      (node (ref "J1") (pin "21") (pinfunction "21_21") (pintype "bidirectional"))
      (node (ref "J1") (pin "23") (pinfunction "23_23") (pintype "bidirectional"))
      (node (ref "J1") (pin "24") (pinfunction "24_24") (pintype "bidirectional"))
      (node (ref "J1") (pin "3") (pinfunction "3_3") (pintype "bidirectional"))
      (node (ref "J1") (pin "5") (pinfunction "5_5") (pintype "bidirectional"))
      (node (ref "J1") (pin "6") (pinfunction "6_6") (pintype "bidirectional"))
      (node (ref "J1") (pin "8") (pinfunction "8_8") (pintype "bidirectional"))
      (node (ref "J1") (pin "9") (pinfunction "9_9") (pintype "bidirectional"))
      (node (ref "J10") (pin "1") (pinfunction "1_1") (pintype "bidirectional"))
      (node (ref "J10") (pin "10") (pinfunction "10_10") (pintype "bidirectional"))
      (node (ref "J10") (pin "13") (pinfunction "13_13") (pintype "bidirectional"))
      (node (ref "J10") (pin "16") (pinfunction "16_16") (pintype "bidirectional"))
      (node (ref "J10") (pin "19") (pinfunction "19_19") (pintype "bidirectional"))
      (node (ref "J10") (pin "22") (pinfunction "22_22") (pintype "bidirectional"))
      (node (ref "J10") (pin "25") (pinfunction "25_25") (pintype "bidirectional"))
      (node (ref "J10") (pin "30") (pinfunction "30_30") (pintype "bidirectional"))
      (node (ref "J10") (pin "4") (pinfunction "4_4") (pintype "bidirectional"))
      (node (ref "J10") (pin "7") (pinfunction "7_7") (pintype "bidirectional"))
      (node (ref "J2") (pin "2") (pinfunction "2_2") (pintype "bidirectional"))
      (node (ref "J5") (pin "2") (pinfunction "2_2") (pintype "bidirectional"))
      (node (ref "J6") (pin "1") (pinfunction "1_1") (pintype "bidirectional"))
      (node (ref "J6") (pin "10") (pinfunction "10_10") (pintype "bidirectional"))
      (node (ref "J6") (pin "13") (pinfunction "13_13") (pintype "bidirectional"))
      (node (ref "J6") (pin "3") (pinfunction "3_3") (pintype "bidirectional"))
      (node (ref "J6") (pin "4") (pinfunction "4_4") (pintype "bidirectional"))
      (node (ref "J6") (pin "6") (pinfunction "6_6") (pintype "bidirectional"))
      (node (ref "J6") (pin "7") (pinfunction "7_7") (pintype "bidirectional"))
      (node (ref "LD2") (pin "1") (pinfunction "C_1") (pintype "passive"))
      (node (ref "LD2") (pin "3") (pinfunction "C_3") (pintype "passive"))
      (node (ref "LD6") (pin "1") (pinfunction "C_1") (pintype "passive"))
      (node (ref "LD6") (pin "3") (pinfunction "C_3") (pintype "passive"))
      (node (ref "LD8") (pin "1") (pinfunction "C_1") (pintype "passive"))
      (node (ref "LD8") (pin "3") (pinfunction "C_3") (pintype "passive"))
      (node (ref "MSBOX2") (pin "1") (pinfunction "1_1") (pintype "passive"))
      (node (ref "MSBOX2") (pin "10") (pinfunction "10_10") (pintype "passive"))
      (node (ref "MSBOX2") (pin "11") (pinfunction "11_11") (pintype "passive"))
      (node (ref "MSBOX2") (pin "12") (pinfunction "12_12") (pintype "passive"))
      (node (ref "MSBOX2") (pin "13") (pinfunction "13_13") (pintype "passive"))
      (node (ref "MSBOX2") (pin "14") (pinfunction "14_14") (pintype "passive"))
      (node (ref "MSBOX2") (pin "15") (pinfunction "15_15") (pintype "passive"))
      (node (ref "MSBOX2") (pin "16") (pinfunction "16_16") (pintype "passive"))
      (node (ref "MSBOX2") (pin "17") (pinfunction "17_17") (pintype "passive"))
      (node (ref "MSBOX2") (pin "18") (pinfunction "18_18") (pintype "passive"))
      (node (ref "MSBOX2") (pin "19") (pinfunction "19_19") (pintype "passive"))
      (node (ref "MSBOX2") (pin "2") (pinfunction "2_2") (pintype "passive"))
      (node (ref "MSBOX2") (pin "20") (pinfunction "20_20") (pintype "passive"))
      (node (ref "MSBOX2") (pin "3") (pinfunction "3_3") (pintype "passive"))
      (node (ref "MSBOX2") (pin "4") (pinfunction "4_4") (pintype "passive"))
      (node (ref "MSBOX2") (pin "5") (pinfunction "5_5") (pintype "passive"))
      (node (ref "MSBOX2") (pin "6") (pinfunction "6_6") (pintype "passive"))
      (node (ref "MSBOX2") (pin "7") (pinfunction "7_7") (pintype "passive"))
      (node (ref "MSBOX2") (pin "8") (pinfunction "8_8") (pintype "passive"))
      (node (ref "MSBOX2") (pin "9") (pinfunction "9_9") (pintype "passive"))
      (node (ref "MSBOX3") (pin "1") (pinfunction "1_1") (pintype "passive"))
      (node (ref "MSBOX3") (pin "10") (pinfunction "10_10") (pintype "passive"))
      (node (ref "MSBOX3") (pin "11") (pinfunction "11_11") (pintype "passive"))
      (node (ref "MSBOX3") (pin "12") (pinfunction "12_12") (pintype "passive"))
      (node (ref "MSBOX3") (pin "13") (pinfunction "13_13") (pintype "passive"))
      (node (ref "MSBOX3") (pin "14") (pinfunction "14_14") (pintype "passive"))
      (node (ref "MSBOX3") (pin "15") (pinfunction "15_15") (pintype "passive"))
      (node (ref "MSBOX3") (pin "16") (pinfunction "16_16") (pintype "passive"))
      (node (ref "MSBOX3") (pin "17") (pinfunction "17_17") (pintype "passive"))
      (node (ref "MSBOX3") (pin "18") (pinfunction "18_18") (pintype "passive"))
      (node (ref "MSBOX3") (pin "19") (pinfunction "19_19") (pintype "passive"))
      (node (ref "MSBOX3") (pin "2") (pinfunction "2_2") (pintype "passive"))
      (node (ref "MSBOX3") (pin "20") (pinfunction "20_20") (pintype "passive"))
      (node (ref "MSBOX3") (pin "3") (pinfunction "3_3") (pintype "passive"))
      (node (ref "MSBOX3") (pin "4") (pinfunction "4_4") (pintype "passive"))
      (node (ref "MSBOX3") (pin "5") (pinfunction "5_5") (pintype "passive"))
      (node (ref "MSBOX3") (pin "6") (pinfunction "6_6") (pintype "passive"))
      (node (ref "MSBOX3") (pin "7") (pinfunction "7_7") (pintype "passive"))
      (node (ref "MSBOX3") (pin "8") (pinfunction "8_8") (pintype "passive"))
      (node (ref "MSBOX3") (pin "9") (pinfunction "9_9") (pintype "passive"))
      (node (ref "R27") (pin "2") (pinfunction "2_2") (pintype "passive"))
      (node (ref "R40") (pin "1") (pinfunction "1_1") (pintype "passive"))
      (node (ref "R46") (pin "1") (pinfunction "1_1") (pintype "passive"))
      (node (ref "R47") (pin "1") (pinfunction "1_1") (pintype "passive"))
      (node (ref "R48") (pin "1") (pinfunction "1_1") (pintype "passive"))
      (node (ref "R67") (pin "2") (pinfunction "2_2") (pintype "passive"))
      (node (ref "R68") (pin "2") (pinfunction "2_2") (pintype "passive"))
      (node (ref "R69") (pin "2") (pinfunction "2_2") (pintype "passive"))
    )
    (net (code "80") (name "N12V0AS") (class "Default")
      (node (ref "J1") (pin "26") (pinfunction "26_26") (pintype "bidirectional"))
      (node (ref "J6") (pin "16") (pinfunction "16_16") (pintype "bidirectional"))
    )
    (net (code "81") (name "Net-(C25-Pad1)") (class "Default")
      (node (ref "C25") (pin "1") (pinfunction "1_1") (pintype "passive"))
      (node (ref "R27") (pin "1") (pinfunction "1_1") (pintype "passive"))
    )
    (net (code "82") (name "Net-(IC14-VCC)") (class "Default")
      (node (ref "C83") (pin "2") (pinfunction "2_2") (pintype "passive"))
      (node (ref "IC14") (pin "4") (pinfunction "VCC_4") (pintype "power_in"))
      (node (ref "IC20") (pin "8") (pinfunction "VCC_8") (pintype "power_in"))
      (node (ref "R105") (pin "1") (pinfunction "1_1") (pintype "passive"))
    )
    (net (code "83") (name "Net-(IC16-A0)") (class "Default")
      (node (ref "IC16") (pin "21") (pinfunction "A0_21") (pintype "input"))
      (node (ref "IC19") (pin "15") (pinfunction "A0_15") (pintype "input"))
      (node (ref "R48") (pin "2") (pinfunction "2_2") (pintype "passive"))
    )
    (net (code "84") (name "Net-(IC16-A1)") (class "Default")
      (node (ref "IC16") (pin "2") (pinfunction "A1_2") (pintype "input"))
      (node (ref "IC19") (pin "16") (pinfunction "A1_16") (pintype "input"))
      (node (ref "R47") (pin "2") (pinfunction "2_2") (pintype "passive"))
    )
    (net (code "85") (name "Net-(IC19-A2)") (class "Default")
      (node (ref "IC19") (pin "17") (pinfunction "A2_17") (pintype "input"))
      (node (ref "R46") (pin "2") (pinfunction "2_2") (pintype "passive"))
    )
    (net (code "86") (name "P3V3s") (class "Default")
      (node (ref "C113") (pin "2") (pinfunction "2_2") (pintype "passive"))
      (node (ref "C146") (pin "2") (pinfunction "2_2") (pintype "passive"))
      (node (ref "IC16") (pin "24") (pinfunction "VDD_24") (pintype "power_in"))
      (node (ref "IC16") (pin "3") (pinfunction "~{RESET}_3") (pintype "input"))
      (node (ref "IC19") (pin "18") (pinfunction "~{RESET}_18") (pintype "input"))
      (node (ref "IC19") (pin "9") (pinfunction "VDD_9") (pintype "power_in"))
      (node (ref "J10") (pin "34") (pinfunction "34_34") (pintype "bidirectional"))
      (node (ref "R105") (pin "2") (pinfunction "2_2") (pintype "passive"))
      (node (ref "R42") (pin "1") (pinfunction "1_1") (pintype "passive"))
      (node (ref "R45") (pin "1") (pinfunction "1_1") (pintype "passive"))
      (node (ref "R88") (pin "1") (pinfunction "1_1") (pintype "passive"))
      (node (ref "R89") (pin "1") (pinfunction "1_1") (pintype "passive"))
    )
    (net (code "87") (name "P12V0") (class "Default")
      (node (ref "J10") (pin "31") (pinfunction "31_31") (pintype "bidirectional"))
      (node (ref "J10") (pin "32") (pinfunction "32_32") (pintype "bidirectional"))
      (node (ref "J10") (pin "33") (pinfunction "33_33") (pintype "bidirectional"))
    )
    (net (code "88") (name "P12V0AS") (class "Default")
      (node (ref "J1") (pin "25") (pinfunction "25_25") (pintype "bidirectional"))
      (node (ref "J6") (pin "15") (pinfunction "15_15") (pintype "bidirectional"))
    )
    (net (code "89") (name "unconnected-(IC14-NC-Pad5)") (class "Default")
      (node (ref "IC14") (pin "5") (pinfunction "NC_5") (pintype "passive"))
    )
    (net (code "90") (name "unconnected-(IC16-~{INT}-Pad1)") (class "Default")
      (node (ref "IC16") (pin "1") (pinfunction "~{INT}_1") (pintype "open_collector"))
    )
    (net (code "91") (name "unconnected-(IC19-INTA-Pad20)") (class "Default")
      (node (ref "IC19") (pin "20") (pinfunction "INTA_20") (pintype "output"))
    )
    (net (code "92") (name "unconnected-(IC19-INTB-Pad19)") (class "Default")
      (node (ref "IC19") (pin "19") (pinfunction "INTB_19") (pintype "output"))
    )
    (net (code "93") (name "unconnected-(IC19-NC-Pad11)") (class "Default")
      (node (ref "IC19") (pin "11") (pinfunction "NC_11") (pintype "passive"))
    )
    (net (code "94") (name "unconnected-(IC19-NC-Pad14)") (class "Default")
      (node (ref "IC19") (pin "14") (pinfunction "NC_14") (pintype "passive"))
    )
    (net (code "95") (name "unconnected-(IC20-A0_(NC)-Pad1)") (class "Default")
      (node (ref "IC20") (pin "1") (pinfunction "A0_(NC)_1") (pintype "input+no_connect"))
    )
    (net (code "96") (name "unconnected-(IC20-A1_(NC)-Pad2)") (class "Default")
      (node (ref "IC20") (pin "2") (pinfunction "A1_(NC)_2") (pintype "input+no_connect"))
    )
    (net (code "97") (name "unconnected-(IC20-A2_(NC)-Pad3)") (class "Default")
      (node (ref "IC20") (pin "3") (pinfunction "A2_(NC)_3") (pintype "input+no_connect"))
    )
    (net (code "98") (name "unconnected-(IC20-NC-Pad7)") (class "Default")
      (node (ref "IC20") (pin "7") (pinfunction "NC_7") (pintype "passive"))
    )
    (net (code "99") (name "unconnected-(J1-Pad22)") (class "Default")
      (node (ref "J1") (pin "22") (pinfunction "22_22") (pintype "bidirectional"))
    )
    (net (code "100") (name "unconnected-(J6-Pad8)") (class "Default")
      (node (ref "J6") (pin "8") (pinfunction "8_8") (pintype "bidirectional"))
    )
    (net (code "101") (name "unconnected-(J6-Pad9)") (class "Default")
      (node (ref "J6") (pin "9") (pinfunction "9_9") (pintype "bidirectional"))
    )
    (net (code "102") (name "unconnected-(J6-Pad11)") (class "Default")
      (node (ref "J6") (pin "11") (pinfunction "11_11") (pintype "bidirectional"))
    )
    (net (code "103") (name "unconnected-(J6-Pad12)") (class "Default")
      (node (ref "J6") (pin "12") (pinfunction "12_12") (pintype "bidirectional"))
    )
    (net (code "104") (name "unconnected-(J6-Pad14)") (class "Default")
      (node (ref "J6") (pin "14") (pinfunction "14_14") (pintype "bidirectional"))
    )
    (net (code "105") (name "unconnected-(J10-Pad11)") (class "Default")
      (node (ref "J10") (pin "11") (pinfunction "11_11") (pintype "bidirectional+no_connect"))
    )
    (net (code "106") (name "unconnected-(J10-Pad23)") (class "Default")
      (node (ref "J10") (pin "23") (pinfunction "23_23") (pintype "bidirectional"))
    )
  )
)
